# LPCB219_-_REFLECT_SENSORS.net
KiCad netlist of a schematic drawn in Altium Designer
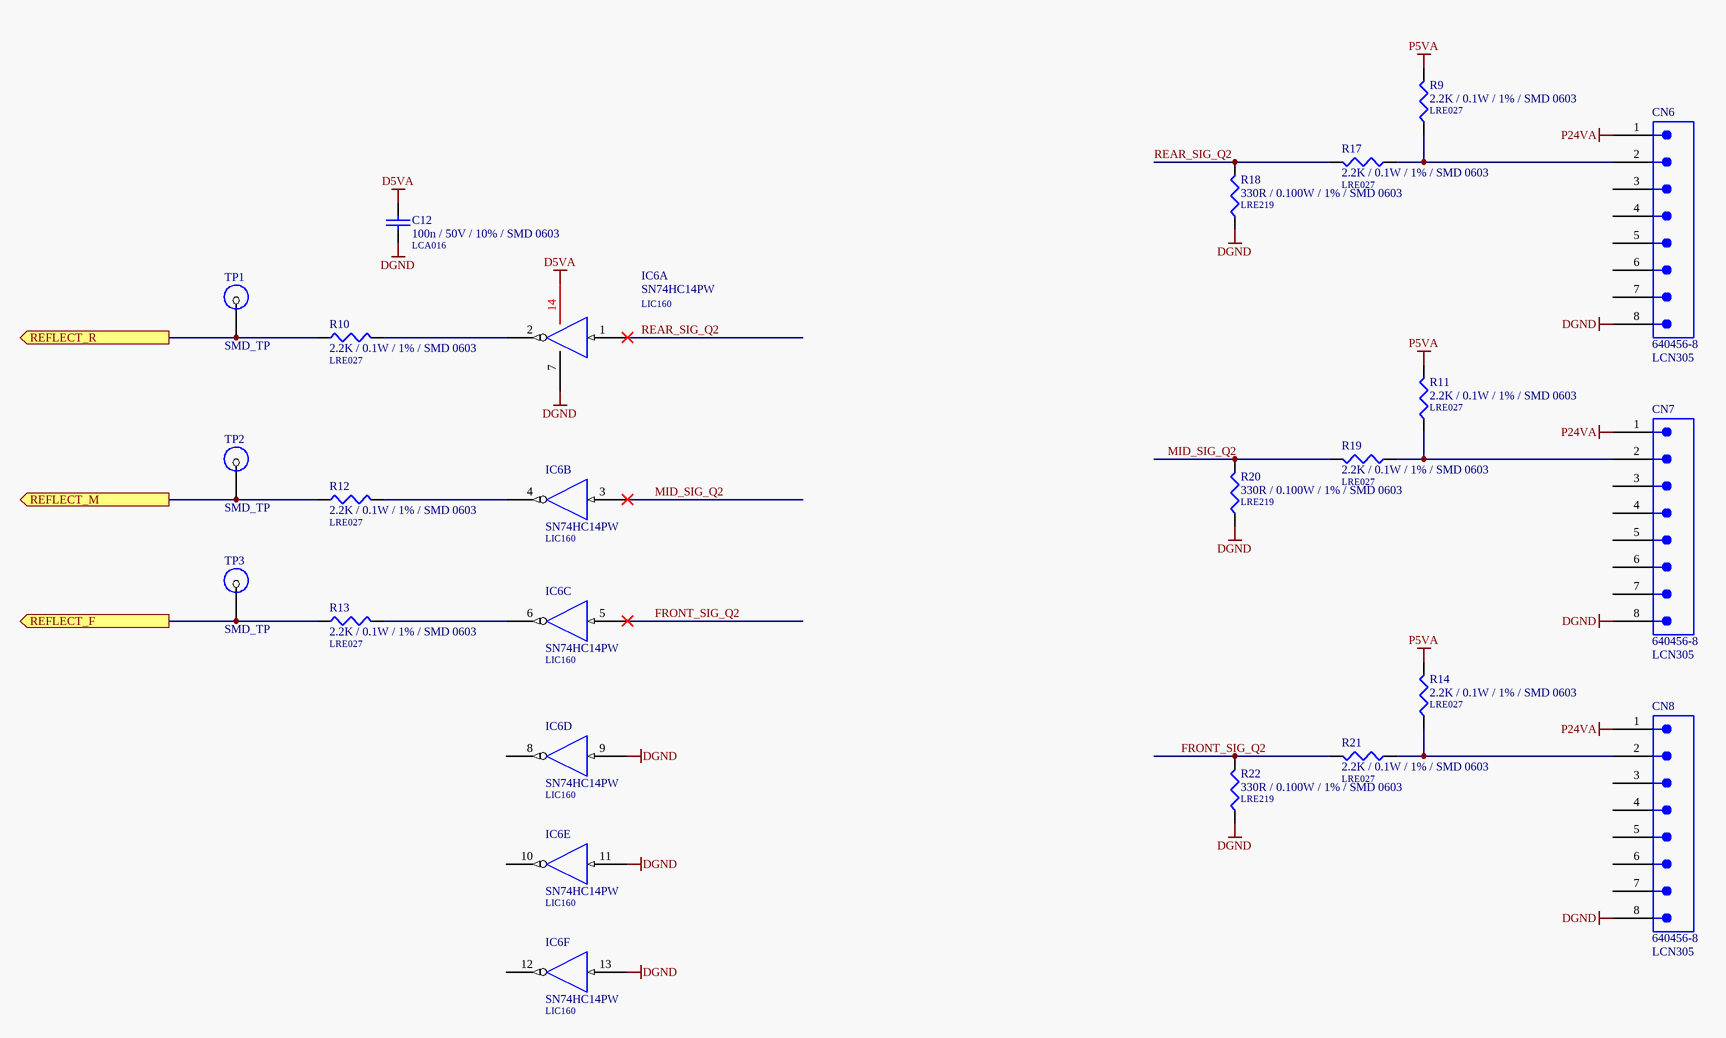
[diagram p0: LPCB219 - REFLECT SENSORS.SchDoc]

(export (version "E")
  (design (tool "Eeschema 10.0.6"))
  (components
    (comp (ref "C12")
      (value "100n / 50V / 10% / SMD 0603")
      (footprint "LFP011__CC1608-0603-IPC7351_B")
      (description "Capacitor, Ceramic Chip, 100nF (0.1uF), 50V, 5%, SMD 0603 [LCA016]")
      (fields (field (name "LDL_NUMBER") "LCA016"))
      (libsource (lib "LDL_Capacitors") (part "100n / 50V / 10% / SMD 0603"))
    )
    (comp (ref "CN6")
      (value "640456-8")
      (footprint "640456-8")
      (description "Connector, Male Header, 8 Way")
      (fields (field (name "LDL_NUMBER") "LCN305"))
      (libsource (lib "LDL_Connectors") (part "640456-8"))
    )
    (comp (ref "CN7")
      (value "640456-8")
      (footprint "640456-8")
      (description "Connector, Male Header, 8 Way")
      (fields (field (name "LDL_NUMBER") "LCN305"))
      (libsource (lib "LDL_Connectors") (part "640456-8"))
    )
    (comp (ref "CN8")
      (value "640456-8")
      (footprint "640456-8")
      (description "Connector, Male Header, 8 Way")
      (fields (field (name "LDL_NUMBER") "LCN305"))
      (libsource (lib "LDL_Connectors") (part "640456-8"))
    )
    (comp (ref "IC6")
      (value "SN74HC14PW")
      (footprint "PW014")
      (description "IC, Hex Inveter, Schmitt Trigger, SMD [LIC160]")
      (fields (field (name "LDL_NUMBER") "LIC160"))
      (libsource (lib "LDL_Semiconductors") (part "SN74HC14PW"))
    )
    (comp (ref "R9")
      (value "2.2K / 0.1W / 1% / SMD 0603")
      (footprint "LFP020__CR1608-0603-IPC7351_B")
      (description "Resistor, Ceramic Chip, 2.2K, 0.1W, 1%, SMD 0603 [LRE027]")
      (fields (field (name "LDL_NUMBER") "LRE027"))
      (libsource (lib "LDL_Resistors") (part "2.2K / 0.1W / 1% / SMD 0603"))
    )
    (comp (ref "R10")
      (value "2.2K / 0.1W / 1% / SMD 0603")
      (footprint "LFP020__CR1608-0603-IPC7351_B")
      (description "Resistor, Ceramic Chip, 2.2K, 0.1W, 1%, SMD 0603 [LRE027]")
      (fields (field (name "LDL_NUMBER") "LRE027"))
      (libsource (lib "LDL_Resistors") (part "2.2K / 0.1W / 1% / SMD 0603"))
    )
    (comp (ref "R11")
      (value "2.2K / 0.1W / 1% / SMD 0603")
      (footprint "LFP020__CR1608-0603-IPC7351_B")
      (description "Resistor, Ceramic Chip, 2.2K, 0.1W, 1%, SMD 0603 [LRE027]")
      (fields (field (name "LDL_NUMBER") "LRE027"))
      (libsource (lib "LDL_Resistors") (part "2.2K / 0.1W / 1% / SMD 0603"))
    )
    (comp (ref "R12")
      (value "2.2K / 0.1W / 1% / SMD 0603")
      (footprint "LFP020__CR1608-0603-IPC7351_B")
      (description "Resistor, Ceramic Chip, 2.2K, 0.1W, 1%, SMD 0603 [LRE027]")
      (fields (field (name "LDL_NUMBER") "LRE027"))
      (libsource (lib "LDL_Resistors") (part "2.2K / 0.1W / 1% / SMD 0603"))
    )
    (comp (ref "R13")
      (value "2.2K / 0.1W / 1% / SMD 0603")
      (footprint "LFP020__CR1608-0603-IPC7351_B")
      (description "Resistor, Ceramic Chip, 2.2K, 0.1W, 1%, SMD 0603 [LRE027]")
      (fields (field (name "LDL_NUMBER") "LRE027"))
      (libsource (lib "LDL_Resistors") (part "2.2K / 0.1W / 1% / SMD 0603"))
    )
    (comp (ref "R14")
      (value "2.2K / 0.1W / 1% / SMD 0603")
      (footprint "LFP020__CR1608-0603-IPC7351_B")
      (description "Resistor, Ceramic Chip, 2.2K, 0.1W, 1%, SMD 0603 [LRE027]")
      (fields (field (name "LDL_NUMBER") "LRE027"))
      (libsource (lib "LDL_Resistors") (part "2.2K / 0.1W / 1% / SMD 0603"))
    )
    (comp (ref "R17")
      (value "2.2K / 0.1W / 1% / SMD 0603")
      (footprint "LFP020__CR1608-0603-IPC7351_B")
      (description "Resistor, Ceramic Chip, 2.2K, 0.1W, 1%, SMD 0603 [LRE027]")
      (fields (field (name "LDL_NUMBER") "LRE027"))
      (libsource (lib "LDL_Resistors") (part "2.2K / 0.1W / 1% / SMD 0603"))
    )
    (comp (ref "R18")
      (value "330R / 0.100W / 1% / SMD 0603")
      (footprint "LFP020__CR1608-0603-IPC7351_B")
      (description "Resistor, Thick Film, 330R, 0.100W, 75V, 1%, SMD 0603 [LRE219]")
      (fields (field (name "LDL_NUMBER") "LRE219"))
      (libsource (lib "LDL_Resistors") (part "330R / 0.100W / 1% / SMD 0603"))
    )
    (comp (ref "R19")
      (value "2.2K / 0.1W / 1% / SMD 0603")
      (footprint "LFP020__CR1608-0603-IPC7351_B")
      (description "Resistor, Ceramic Chip, 2.2K, 0.1W, 1%, SMD 0603 [LRE027]")
      (fields (field (name "LDL_NUMBER") "LRE027"))
      (libsource (lib "LDL_Resistors") (part "2.2K / 0.1W / 1% / SMD 0603"))
    )
    (comp (ref "R20")
      (value "330R / 0.100W / 1% / SMD 0603")
      (footprint "LFP020__CR1608-0603-IPC7351_B")
      (description "Resistor, Thick Film, 330R, 0.100W, 75V, 1%, SMD 0603 [LRE219]")
      (fields (field (name "LDL_NUMBER") "LRE219"))
      (libsource (lib "LDL_Resistors") (part "330R / 0.100W / 1% / SMD 0603"))
    )
    (comp (ref "R21")
      (value "2.2K / 0.1W / 1% / SMD 0603")
      (footprint "LFP020__CR1608-0603-IPC7351_B")
      (description "Resistor, Ceramic Chip, 2.2K, 0.1W, 1%, SMD 0603 [LRE027]")
      (fields (field (name "LDL_NUMBER") "LRE027"))
      (libsource (lib "LDL_Resistors") (part "2.2K / 0.1W / 1% / SMD 0603"))
    )
    (comp (ref "R22")
      (value "330R / 0.100W / 1% / SMD 0603")
      (footprint "LFP020__CR1608-0603-IPC7351_B")
      (description "Resistor, Thick Film, 330R, 0.100W, 75V, 1%, SMD 0603 [LRE219]")
      (fields (field (name "LDL_NUMBER") "LRE219"))
      (libsource (lib "LDL_Resistors") (part "330R / 0.100W / 1% / SMD 0603"))
    )
    (comp (ref "TP1")
      (value "SMD_TP")
      (footprint "SMD-TP")
      (description "SMD Test Point")
      (libsource (lib "LDL_Connectors") (part "SMD_TP"))
    )
    (comp (ref "TP2")
      (value "SMD_TP")
      (footprint "SMD-TP")
      (description "SMD Test Point")
      (libsource (lib "LDL_Connectors") (part "SMD_TP"))
    )
    (comp (ref "TP3")
      (value "SMD_TP")
      (footprint "SMD-TP")
      (description "SMD Test Point")
      (libsource (lib "LDL_Connectors") (part "SMD_TP"))
    )
  )
  (nets
    (net (code "1") (name "/FRONT_SIG_Q2") (class "Default")
      (node (ref "IC6") (pin "5") (pinfunction "A_5") (pintype "input"))
      (node (ref "R21") (pin "2") (pintype "passive"))
      (node (ref "R22") (pin "2") (pintype "passive"))
    )
    (net (code "2") (name "/MID_SIG_Q2") (class "Default")
      (node (ref "IC6") (pin "3") (pinfunction "A_3") (pintype "input"))
      (node (ref "R19") (pin "2") (pintype "passive"))
      (node (ref "R20") (pin "2") (pintype "passive"))
    )
    (net (code "3") (name "/REAR_SIG_Q2") (class "Default")
      (node (ref "IC6") (pin "1") (pinfunction "A_1") (pintype "input"))
      (node (ref "R17") (pin "2") (pintype "passive"))
      (node (ref "R18") (pin "2") (pintype "passive"))
    )
    (net (code "4") (name "/REFLECT_F") (class "Default")
      (node (ref "R13") (pin "1") (pintype "passive"))
      (node (ref "TP3") (pin "1") (pintype "passive"))
    )
    (net (code "5") (name "/REFLECT_M") (class "Default")
      (node (ref "R12") (pin "1") (pintype "passive"))
      (node (ref "TP2") (pin "1") (pintype "passive"))
    )
    (net (code "6") (name "/REFLECT_R") (class "Default")
      (node (ref "R10") (pin "1") (pintype "passive"))
      (node (ref "TP1") (pin "1") (pintype "passive"))
    )
    (net (code "7") (name "D5VA") (class "Default")
      (node (ref "C12") (pin "1") (pintype "passive"))
      (node (ref "IC6") (pin "14") (pinfunction "VCC_14") (pintype "power_in"))
    )
    (net (code "8") (name "DGND") (class "Default")
      (node (ref "C12") (pin "2") (pintype "passive"))
      (node (ref "CN6") (pin "8") (pinfunction "8_8") (pintype "passive"))
      (node (ref "CN7") (pin "8") (pinfunction "8_8") (pintype "passive"))
      (node (ref "CN8") (pin "8") (pinfunction "8_8") (pintype "passive"))
      (node (ref "IC6") (pin "11") (pinfunction "A_11") (pintype "input"))
      (node (ref "IC6") (pin "13") (pinfunction "A_13") (pintype "input"))
      (node (ref "IC6") (pin "7") (pinfunction "GND_7") (pintype "power_in"))
      (node (ref "IC6") (pin "9") (pinfunction "A_9") (pintype "input"))
      (node (ref "R18") (pin "1") (pintype "passive"))
      (node (ref "R20") (pin "1") (pintype "passive"))
      (node (ref "R22") (pin "1") (pintype "passive"))
    )
    (net (code "9") (name "Net-(CN6-Pad2)") (class "Default")
      (node (ref "CN6") (pin "2") (pinfunction "2_2") (pintype "passive"))
      (node (ref "R17") (pin "1") (pintype "passive"))
      (node (ref "R9") (pin "1") (pintype "passive"))
    )
    (net (code "10") (name "Net-(CN7-Pad2)") (class "Default")
      (node (ref "CN7") (pin "2") (pinfunction "2_2") (pintype "passive"))
      (node (ref "R11") (pin "1") (pintype "passive"))
      (node (ref "R19") (pin "1") (pintype "passive"))
    )
    (net (code "11") (name "Net-(CN8-Pad2)") (class "Default")
      (node (ref "CN8") (pin "2") (pinfunction "2_2") (pintype "passive"))
      (node (ref "R14") (pin "1") (pintype "passive"))
      (node (ref "R21") (pin "1") (pintype "passive"))
    )
    (net (code "12") (name "Net-(IC6A-Y)") (class "Default")
      (node (ref "IC6") (pin "2") (pinfunction "Y_2") (pintype "output"))
      (node (ref "R10") (pin "2") (pintype "passive"))
    )
    (net (code "13") (name "Net-(IC6B-Y)") (class "Default")
      (node (ref "IC6") (pin "4") (pinfunction "Y_4") (pintype "output"))
      (node (ref "R12") (pin "2") (pintype "passive"))
    )
    (net (code "14") (name "Net-(IC6C-Y)") (class "Default")
      (node (ref "IC6") (pin "6") (pinfunction "Y_6") (pintype "output"))
      (node (ref "R13") (pin "2") (pintype "passive"))
    )
    (net (code "15") (name "P5VA") (class "Default")
      (node (ref "R11") (pin "2") (pintype "passive"))
      (node (ref "R14") (pin "2") (pintype "passive"))
      (node (ref "R9") (pin "2") (pintype "passive"))
    )
    (net (code "16") (name "P24VA") (class "Default")
      (node (ref "CN6") (pin "1") (pinfunction "1_1") (pintype "passive"))
      (node (ref "CN7") (pin "1") (pinfunction "1_1") (pintype "passive"))
      (node (ref "CN8") (pin "1") (pinfunction "1_1") (pintype "passive"))
    )
    (net (code "17") (name "unconnected-(CN6-Pad3)") (class "Default")
      (node (ref "CN6") (pin "3") (pinfunction "3_3") (pintype "passive"))
    )
    (net (code "18") (name "unconnected-(CN6-Pad4)") (class "Default")
      (node (ref "CN6") (pin "4") (pinfunction "4_4") (pintype "passive"))
    )
    (net (code "19") (name "unconnected-(CN6-Pad5)") (class "Default")
      (node (ref "CN6") (pin "5") (pinfunction "5_5") (pintype "passive"))
    )
    (net (code "20") (name "unconnected-(CN6-Pad6)") (class "Default")
      (node (ref "CN6") (pin "6") (pinfunction "6_6") (pintype "passive"))
    )
    (net (code "21") (name "unconnected-(CN6-Pad7)") (class "Default")
      (node (ref "CN6") (pin "7") (pinfunction "7_7") (pintype "passive"))
    )
    (net (code "22") (name "unconnected-(CN7-Pad3)") (class "Default")
      (node (ref "CN7") (pin "3") (pinfunction "3_3") (pintype "passive"))
    )
    (net (code "23") (name "unconnected-(CN7-Pad4)") (class "Default")
      (node (ref "CN7") (pin "4") (pinfunction "4_4") (pintype "passive"))
    )
    (net (code "24") (name "unconnected-(CN7-Pad5)") (class "Default")
      (node (ref "CN7") (pin "5") (pinfunction "5_5") (pintype "passive"))
    )
    (net (code "25") (name "unconnected-(CN7-Pad6)") (class "Default")
      (node (ref "CN7") (pin "6") (pinfunction "6_6") (pintype "passive"))
    )
    (net (code "26") (name "unconnected-(CN7-Pad7)") (class "Default")
      (node (ref "CN7") (pin "7") (pinfunction "7_7") (pintype "passive"))
    )
    (net (code "27") (name "unconnected-(CN8-Pad3)") (class "Default")
      (node (ref "CN8") (pin "3") (pinfunction "3_3") (pintype "passive"))
    )
    (net (code "28") (name "unconnected-(CN8-Pad4)") (class "Default")
      (node (ref "CN8") (pin "4") (pinfunction "4_4") (pintype "passive"))
    )
    (net (code "29") (name "unconnected-(CN8-Pad5)") (class "Default")
      (node (ref "CN8") (pin "5") (pinfunction "5_5") (pintype "passive"))
    )
    (net (code "30") (name "unconnected-(CN8-Pad6)") (class "Default")
      (node (ref "CN8") (pin "6") (pinfunction "6_6") (pintype "passive"))
    )
    (net (code "31") (name "unconnected-(CN8-Pad7)") (class "Default")
      (node (ref "CN8") (pin "7") (pinfunction "7_7") (pintype "passive"))
    )
    (net (code "32") (name "unconnected-(IC6D-Y-Pad8)") (class "Default")
      (node (ref "IC6") (pin "8") (pinfunction "Y_8") (pintype "output"))
    )
    (net (code "33") (name "unconnected-(IC6E-Y-Pad10)") (class "Default")
      (node (ref "IC6") (pin "10") (pinfunction "Y_10") (pintype "output"))
    )
    (net (code "34") (name "unconnected-(IC6F-Y-Pad12)") (class "Default")
      (node (ref "IC6") (pin "12") (pinfunction "Y_12") (pintype "output"))
    )
  )
)
